# Peripherals.net
KiCad netlist of a schematic drawn in Altium Designer
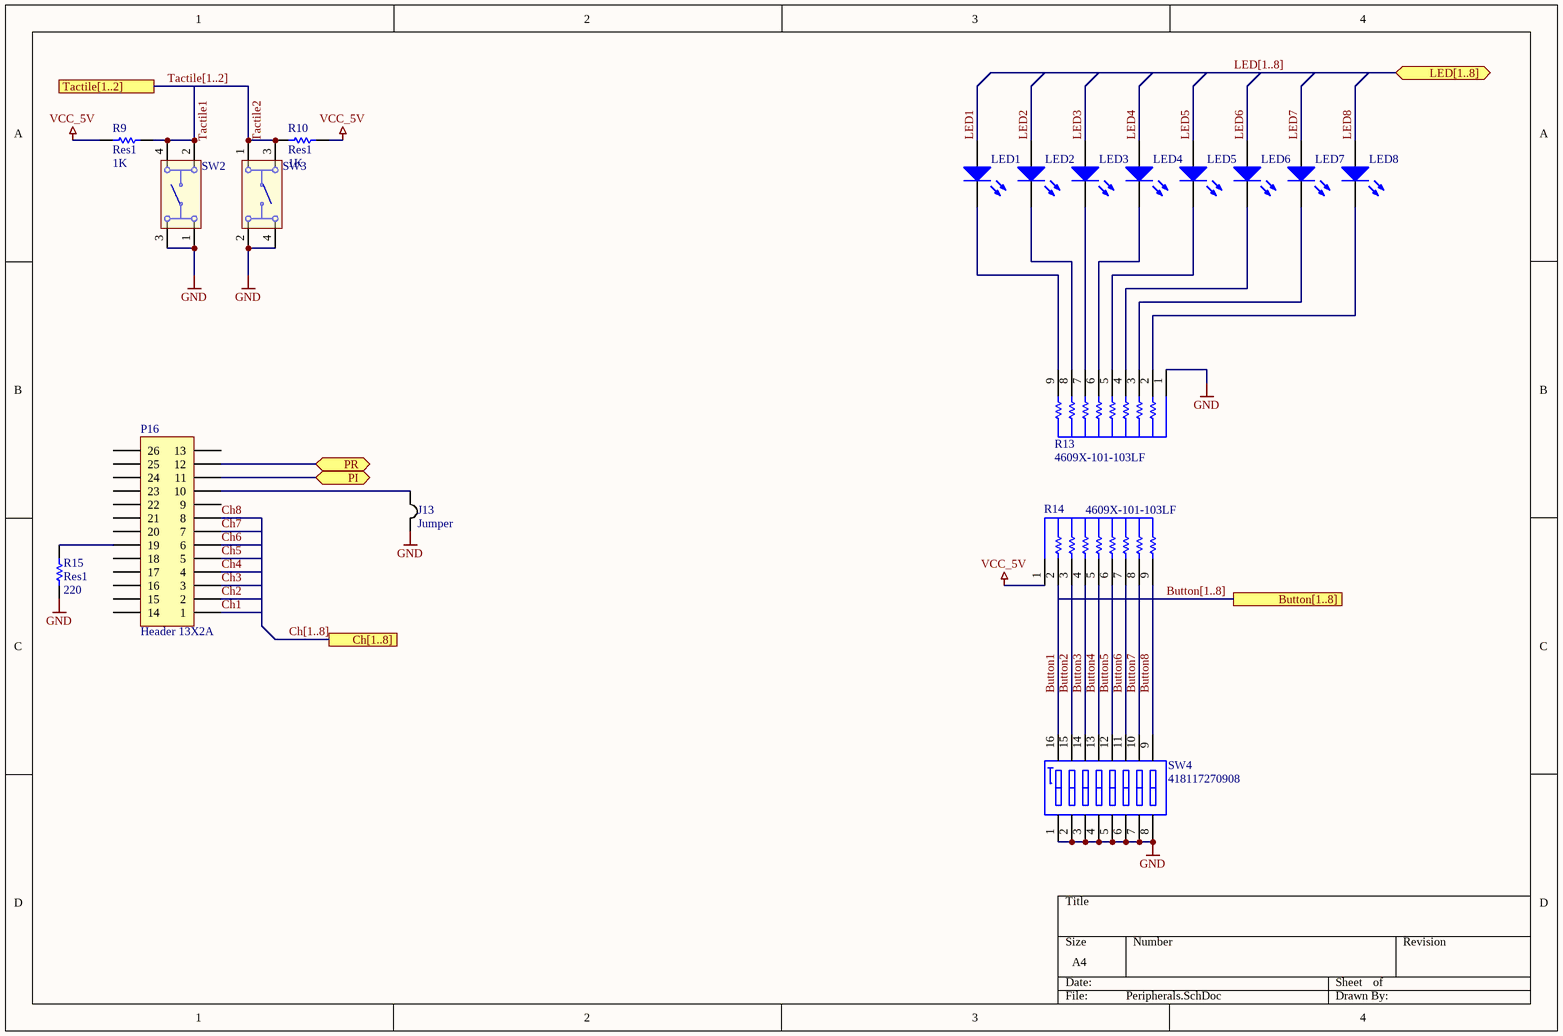
[diagram p0: Peripherals.SchDoc]

(export (version "E")
  (design (tool "Eeschema 10.0.6"))
  (components
    (comp (ref "J13")
      (value "Jumper")
      (footprint "SMDJumper")
      (libsource (lib "DS1E-S-DC3V") (part "Jumper"))
    )
    (comp (ref "LED1")
      (value "TX1")
      (footprint "Type 3mm")
      (description "THT LED round mono-color waterclear, WL-TMRW, Yellow")
      (fields (field (name "MANUFACTURER") "Wuerth Elektronik") (field (name "PARTNUMBER") "151033YS03000"))
      (libsource (lib "Altium Content Vault") (part "WE-LED_K1A2-2"))
    )
    (comp (ref "LED2")
      (value "TX1")
      (footprint "Type 3mm")
      (description "THT LED round mono-color waterclear, WL-TMRW, Yellow")
      (fields (field (name "MANUFACTURER") "Wuerth Elektronik") (field (name "PARTNUMBER") "151033YS03000"))
      (libsource (lib "Altium Content Vault") (part "WE-LED_K1A2-2"))
    )
    (comp (ref "LED3")
      (value "TX1")
      (footprint "Type 3mm")
      (description "THT LED round mono-color waterclear, WL-TMRW, Yellow")
      (fields (field (name "MANUFACTURER") "Wuerth Elektronik") (field (name "PARTNUMBER") "151033YS03000"))
      (libsource (lib "Altium Content Vault") (part "WE-LED_K1A2-2"))
    )
    (comp (ref "LED4")
      (value "TX1")
      (footprint "Type 3mm")
      (description "THT LED round mono-color waterclear, WL-TMRW, Yellow")
      (fields (field (name "MANUFACTURER") "Wuerth Elektronik") (field (name "PARTNUMBER") "151033YS03000"))
      (libsource (lib "Altium Content Vault") (part "WE-LED_K1A2-2"))
    )
    (comp (ref "LED5")
      (value "TX1")
      (footprint "Type 3mm")
      (description "THT LED round mono-color waterclear, WL-TMRW, Yellow")
      (fields (field (name "MANUFACTURER") "Wuerth Elektronik") (field (name "PARTNUMBER") "151033YS03000"))
      (libsource (lib "Altium Content Vault") (part "WE-LED_K1A2-2"))
    )
    (comp (ref "LED6")
      (value "TX1")
      (footprint "Type 3mm")
      (description "THT LED round mono-color waterclear, WL-TMRW, Yellow")
      (fields (field (name "MANUFACTURER") "Wuerth Elektronik") (field (name "PARTNUMBER") "151033YS03000"))
      (libsource (lib "Altium Content Vault") (part "WE-LED_K1A2-2"))
    )
    (comp (ref "LED7")
      (value "TX1")
      (footprint "Type 3mm")
      (description "THT LED round mono-color waterclear, WL-TMRW, Yellow")
      (fields (field (name "MANUFACTURER") "Wuerth Elektronik") (field (name "PARTNUMBER") "151033YS03000"))
      (libsource (lib "Altium Content Vault") (part "WE-LED_K1A2-2"))
    )
    (comp (ref "LED8")
      (value "TX1")
      (footprint "Type 3mm")
      (description "THT LED round mono-color waterclear, WL-TMRW, Yellow")
      (fields (field (name "MANUFACTURER") "Wuerth Elektronik") (field (name "PARTNUMBER") "151033YS03000"))
      (libsource (lib "Altium Content Vault") (part "WE-LED_K1A2-2"))
    )
    (comp (ref "P16")
      (value "Header 13X2A")
      (footprint "HDR2X13_CEN")
      (description "Header, 13-Pin, Dual row")
      (fields (field (name "PUBLISHER") "Altium Limited"))
      (libsource (lib "Miscellaneous Connectors") (part "Header 13X2A"))
    )
    (comp (ref "R9")
      (value "Res1")
      (footprint "AXIAL-0.3")
      (description "Resistor")
      (fields (field (name "ALTIUM_VALUE") "1K") (field (name "PUBLISHER") "Altium Limited"))
      (libsource (lib "Miscellaneous Devices") (part "Res1"))
    )
    (comp (ref "R10")
      (value "Res1")
      (footprint "AXIAL-0.3")
      (description "Resistor")
      (fields (field (name "ALTIUM_VALUE") "1K") (field (name "PUBLISHER") "Altium Limited"))
      (libsource (lib "Miscellaneous Devices") (part "Res1"))
    )
    (comp (ref "R13")
      (value "4609X-101-103LF")
      (footprint "BOUR-4609X")
      (description "Resistor, Network, 1.13 W, 10 kOhm, -55 to 125 degC, 9-Pin THD, RoHS, Bulk")
      (fields (field (name "TOLERANCE") "±2%") (field (name "MANUFACTURER") "Bourns"))
      (libsource (lib "Altium Content Vault") (part "RES-BUS-9"))
    )
    (comp (ref "R14")
      (value "4609X-101-103LF")
      (footprint "BOUR-4609X")
      (description "Resistor, Network, 1.13 W, 10 kOhm, -55 to 125 degC, 9-Pin THD, RoHS, Bulk")
      (fields (field (name "TOLERANCE") "±2%") (field (name "MANUFACTURER") "Bourns"))
      (libsource (lib "Altium Content Vault") (part "RES-BUS-9"))
    )
    (comp (ref "R15")
      (value "Res1")
      (footprint "AXIAL-0.3")
      (description "Resistor")
      (fields (field (name "ALTIUM_VALUE") "220") (field (name "PUBLISHER") "Altium Limited"))
      (libsource (lib "Miscellaneous Devices") (part "Res1"))
    )
    (comp (ref "SW2")
      (value "430156130726")
      (footprint "430156130726")
      (description "WS-TATV THT Tact Switch 6X6 mm")
      (fields (field (name "MANUFACTURER") "Wuerth Elektronik"))
      (libsource (lib "Altium Content Vault") (part "WE-TACT-SW-4"))
    )
    (comp (ref "SW3")
      (value "430156130726")
      (footprint "430156130726")
      (description "WS-TATV THT Tact Switch 6X6 mm")
      (fields (field (name "MANUFACTURER") "Wuerth Elektronik"))
      (libsource (lib "") (part "WE-TACT-SW-4_1"))
    )
    (comp (ref "SW4")
      (value "418117270908")
      (footprint "418117270908")
      (description "WS-DITV 2.54 mm Compact THT Dip Switch with Raised Actuator")
      (fields (field (name "MANUFACTURER") "Wuerth Elektronik"))
      (libsource (lib "Altium Content Vault") (part "WE-DIP-SW-16"))
    )
  )
  (nets
    (net (code "1") (name "/Button1") (class "Default")
      (node (ref "R14") (pin "2") (pinfunction "2_2") (pintype "passive"))
      (node (ref "SW4") (pin "16") (pinfunction "16_16") (pintype "passive"))
    )
    (net (code "2") (name "/Button2") (class "Default")
      (node (ref "R14") (pin "3") (pinfunction "3_3") (pintype "passive"))
      (node (ref "SW4") (pin "15") (pinfunction "15_15") (pintype "passive"))
    )
    (net (code "3") (name "/Button3") (class "Default")
      (node (ref "R14") (pin "4") (pinfunction "4_4") (pintype "passive"))
      (node (ref "SW4") (pin "14") (pinfunction "14_14") (pintype "passive"))
    )
    (net (code "4") (name "/Button4") (class "Default")
      (node (ref "R14") (pin "5") (pinfunction "5_5") (pintype "passive"))
      (node (ref "SW4") (pin "13") (pinfunction "13_13") (pintype "passive"))
    )
    (net (code "5") (name "/Button5") (class "Default")
      (node (ref "R14") (pin "6") (pinfunction "6_6") (pintype "passive"))
      (node (ref "SW4") (pin "12") (pinfunction "12_12") (pintype "passive"))
    )
    (net (code "6") (name "/Button6") (class "Default")
      (node (ref "R14") (pin "7") (pinfunction "7_7") (pintype "passive"))
      (node (ref "SW4") (pin "11") (pinfunction "11_11") (pintype "passive"))
    )
    (net (code "7") (name "/Button7") (class "Default")
      (node (ref "R14") (pin "8") (pinfunction "8_8") (pintype "passive"))
      (node (ref "SW4") (pin "10") (pinfunction "10_10") (pintype "passive"))
    )
    (net (code "8") (name "/Button8") (class "Default")
      (node (ref "R14") (pin "9") (pinfunction "9_9") (pintype "passive"))
      (node (ref "SW4") (pin "9") (pinfunction "9_9") (pintype "passive"))
    )
    (net (code "10") (name "/Ch1") (class "Default")
      (node (ref "P16") (pin "1") (pinfunction "1_1") (pintype "passive"))
    )
    (net (code "11") (name "/Ch2") (class "Default")
      (node (ref "P16") (pin "2") (pinfunction "2_2") (pintype "passive"))
    )
    (net (code "12") (name "/Ch3") (class "Default")
      (node (ref "P16") (pin "3") (pinfunction "3_3") (pintype "passive"))
    )
    (net (code "13") (name "/Ch4") (class "Default")
      (node (ref "P16") (pin "4") (pinfunction "4_4") (pintype "passive"))
    )
    (net (code "14") (name "/Ch5") (class "Default")
      (node (ref "P16") (pin "5") (pinfunction "5_5") (pintype "passive"))
    )
    (net (code "15") (name "/Ch6") (class "Default")
      (node (ref "P16") (pin "6") (pinfunction "6_6") (pintype "passive"))
    )
    (net (code "16") (name "/Ch7") (class "Default")
      (node (ref "P16") (pin "7") (pinfunction "7_7") (pintype "passive"))
    )
    (net (code "17") (name "/Ch8") (class "Default")
      (node (ref "P16") (pin "8") (pinfunction "8_8") (pintype "passive"))
    )
    (net (code "19") (name "/LED1") (class "Default")
      (node (ref "LED1") (pin "2") (pinfunction "A_2") (pintype "passive"))
    )
    (net (code "20") (name "/LED2") (class "Default")
      (node (ref "LED2") (pin "2") (pinfunction "A_2") (pintype "passive"))
    )
    (net (code "21") (name "/LED3") (class "Default")
      (node (ref "LED3") (pin "2") (pinfunction "A_2") (pintype "passive"))
    )
    (net (code "22") (name "/LED4") (class "Default")
      (node (ref "LED4") (pin "2") (pinfunction "A_2") (pintype "passive"))
    )
    (net (code "23") (name "/LED5") (class "Default")
      (node (ref "LED5") (pin "2") (pinfunction "A_2") (pintype "passive"))
    )
    (net (code "24") (name "/LED6") (class "Default")
      (node (ref "LED6") (pin "2") (pinfunction "A_2") (pintype "passive"))
    )
    (net (code "25") (name "/LED7") (class "Default")
      (node (ref "LED7") (pin "2") (pinfunction "A_2") (pintype "passive"))
    )
    (net (code "26") (name "/LED8") (class "Default")
      (node (ref "LED8") (pin "2") (pinfunction "A_2") (pintype "passive"))
    )
    (net (code "28") (name "/PI") (class "Default")
      (node (ref "P16") (pin "11") (pinfunction "11_11") (pintype "passive"))
    )
    (net (code "29") (name "/PR") (class "Default")
      (node (ref "P16") (pin "12") (pinfunction "12_12") (pintype "passive"))
    )
    (net (code "30") (name "/Tactile1") (class "Default")
      (node (ref "R9") (pin "2") (pinfunction "2_2") (pintype "passive"))
      (node (ref "SW2") (pin "2") (pinfunction "2_2") (pintype "passive"))
      (node (ref "SW2") (pin "4") (pinfunction "4_4") (pintype "passive"))
    )
    (net (code "31") (name "/Tactile2") (class "Default")
      (node (ref "R10") (pin "1") (pinfunction "1_1") (pintype "passive"))
      (node (ref "SW3") (pin "1") (pinfunction "1_1") (pintype "passive"))
      (node (ref "SW3") (pin "3") (pinfunction "3_3") (pintype "passive"))
    )
    (net (code "33") (name "GND") (class "Default")
      (node (ref "J13") (pin "2") (pinfunction "2_2") (pintype "passive"))
      (node (ref "R13") (pin "1") (pinfunction "1_1") (pintype "passive"))
      (node (ref "R15") (pin "1") (pinfunction "1_1") (pintype "passive"))
      (node (ref "SW2") (pin "1") (pinfunction "1_1") (pintype "passive"))
      (node (ref "SW2") (pin "3") (pinfunction "3_3") (pintype "passive"))
      (node (ref "SW3") (pin "2") (pinfunction "2_2") (pintype "passive"))
      (node (ref "SW3") (pin "4") (pinfunction "4_4") (pintype "passive"))
      (node (ref "SW4") (pin "1") (pinfunction "1_1") (pintype "passive"))
      (node (ref "SW4") (pin "2") (pinfunction "2_2") (pintype "passive"))
      (node (ref "SW4") (pin "3") (pinfunction "3_3") (pintype "passive"))
      (node (ref "SW4") (pin "4") (pinfunction "4_4") (pintype "passive"))
      (node (ref "SW4") (pin "5") (pinfunction "5_5") (pintype "passive"))
      (node (ref "SW4") (pin "6") (pinfunction "6_6") (pintype "passive"))
      (node (ref "SW4") (pin "7") (pinfunction "7_7") (pintype "passive"))
      (node (ref "SW4") (pin "8") (pinfunction "8_8") (pintype "passive"))
    )
    (net (code "34") (name "Net-(J13-Pad1)") (class "Default")
      (node (ref "J13") (pin "1") (pinfunction "1_1") (pintype "passive"))
      (node (ref "P16") (pin "10") (pinfunction "10_10") (pintype "passive"))
    )
    (net (code "35") (name "Net-(LED1-K)") (class "Default")
      (node (ref "LED1") (pin "1") (pinfunction "K_1") (pintype "passive"))
      (node (ref "R13") (pin "9") (pinfunction "9_9") (pintype "passive"))
    )
    (net (code "36") (name "Net-(LED2-K)") (class "Default")
      (node (ref "LED2") (pin "1") (pinfunction "K_1") (pintype "passive"))
      (node (ref "R13") (pin "8") (pinfunction "8_8") (pintype "passive"))
    )
    (net (code "37") (name "Net-(LED3-K)") (class "Default")
      (node (ref "LED3") (pin "1") (pinfunction "K_1") (pintype "passive"))
      (node (ref "R13") (pin "7") (pinfunction "7_7") (pintype "passive"))
    )
    (net (code "38") (name "Net-(LED4-K)") (class "Default")
      (node (ref "LED4") (pin "1") (pinfunction "K_1") (pintype "passive"))
      (node (ref "R13") (pin "6") (pinfunction "6_6") (pintype "passive"))
    )
    (net (code "39") (name "Net-(LED5-K)") (class "Default")
      (node (ref "LED5") (pin "1") (pinfunction "K_1") (pintype "passive"))
      (node (ref "R13") (pin "5") (pinfunction "5_5") (pintype "passive"))
    )
    (net (code "40") (name "Net-(LED6-K)") (class "Default")
      (node (ref "LED6") (pin "1") (pinfunction "K_1") (pintype "passive"))
      (node (ref "R13") (pin "4") (pinfunction "4_4") (pintype "passive"))
    )
    (net (code "41") (name "Net-(LED7-K)") (class "Default")
      (node (ref "LED7") (pin "1") (pinfunction "K_1") (pintype "passive"))
      (node (ref "R13") (pin "3") (pinfunction "3_3") (pintype "passive"))
    )
    (net (code "42") (name "Net-(LED8-K)") (class "Default")
      (node (ref "LED8") (pin "1") (pinfunction "K_1") (pintype "passive"))
      (node (ref "R13") (pin "2") (pinfunction "2_2") (pintype "passive"))
    )
    (net (code "43") (name "Net-(P16-Pad19)") (class "Default")
      (node (ref "P16") (pin "19") (pinfunction "19_19") (pintype "passive"))
      (node (ref "R15") (pin "2") (pinfunction "2_2") (pintype "passive"))
    )
    (net (code "44") (name "VCC_5V") (class "Default")
      (node (ref "R10") (pin "2") (pinfunction "2_2") (pintype "passive"))
      (node (ref "R14") (pin "1") (pinfunction "1_1") (pintype "passive"))
      (node (ref "R9") (pin "1") (pinfunction "1_1") (pintype "passive"))
    )
    (net (code "45") (name "unconnected-(P16-Pad9)") (class "Default")
      (node (ref "P16") (pin "9") (pinfunction "9_9") (pintype "passive"))
    )
    (net (code "46") (name "unconnected-(P16-Pad13)") (class "Default")
      (node (ref "P16") (pin "13") (pinfunction "13_13") (pintype "passive"))
    )
    (net (code "47") (name "unconnected-(P16-Pad14)") (class "Default")
      (node (ref "P16") (pin "14") (pinfunction "14_14") (pintype "passive"))
    )
    (net (code "48") (name "unconnected-(P16-Pad15)") (class "Default")
      (node (ref "P16") (pin "15") (pinfunction "15_15") (pintype "passive"))
    )
    (net (code "49") (name "unconnected-(P16-Pad16)") (class "Default")
      (node (ref "P16") (pin "16") (pinfunction "16_16") (pintype "passive"))
    )
    (net (code "50") (name "unconnected-(P16-Pad17)") (class "Default")
      (node (ref "P16") (pin "17") (pinfunction "17_17") (pintype "passive"))
    )
    (net (code "51") (name "unconnected-(P16-Pad18)") (class "Default")
      (node (ref "P16") (pin "18") (pinfunction "18_18") (pintype "passive"))
    )
    (net (code "52") (name "unconnected-(P16-Pad20)") (class "Default")
      (node (ref "P16") (pin "20") (pinfunction "20_20") (pintype "passive"))
    )
    (net (code "53") (name "unconnected-(P16-Pad21)") (class "Default")
      (node (ref "P16") (pin "21") (pinfunction "21_21") (pintype "passive"))
    )
    (net (code "54") (name "unconnected-(P16-Pad22)") (class "Default")
      (node (ref "P16") (pin "22") (pinfunction "22_22") (pintype "passive"))
    )
    (net (code "55") (name "unconnected-(P16-Pad23)") (class "Default")
      (node (ref "P16") (pin "23") (pinfunction "23_23") (pintype "passive"))
    )
    (net (code "56") (name "unconnected-(P16-Pad24)") (class "Default")
      (node (ref "P16") (pin "24") (pinfunction "24_24") (pintype "passive"))
    )
    (net (code "57") (name "unconnected-(P16-Pad25)") (class "Default")
      (node (ref "P16") (pin "25") (pinfunction "25_25") (pintype "passive"))
    )
    (net (code "58") (name "unconnected-(P16-Pad26)") (class "Default")
      (node (ref "P16") (pin "26") (pinfunction "26_26") (pintype "passive"))
    )
  )
)
